# led_module.net
KiCad netlist of a schematic drawn in EAGLE
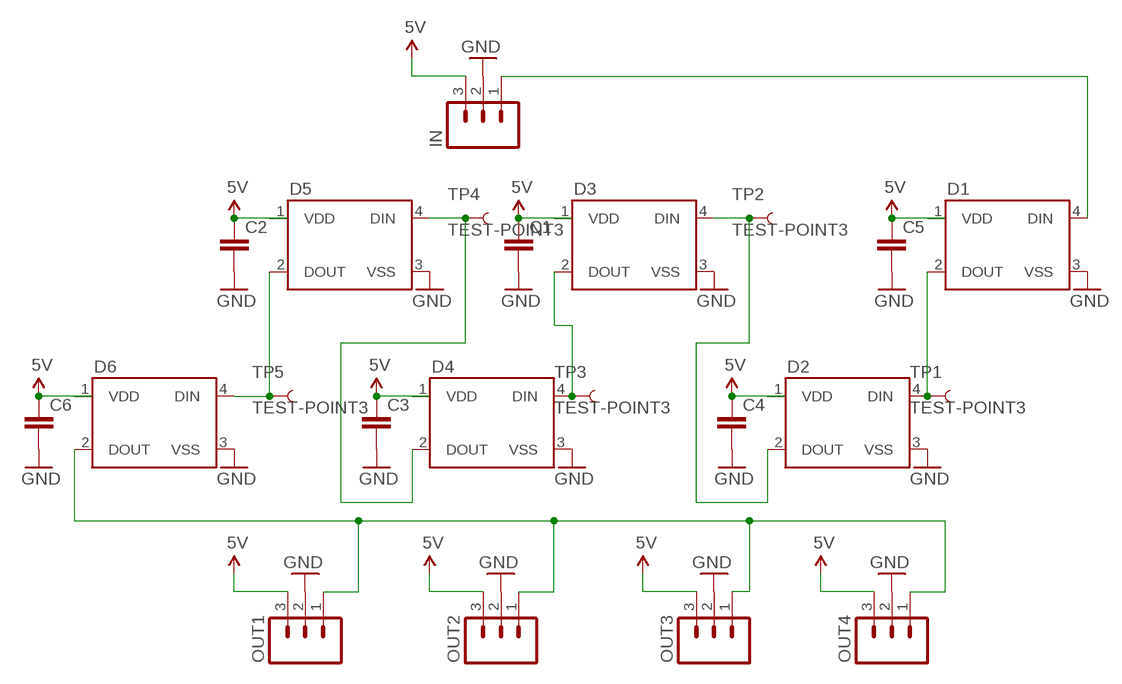
[diagram p0: schematic, sheet 1]

(export (version "E")
  (design (tool "Eeschema 10.0.6"))
  (components
    (comp (ref "C1")
      (value "CAP0805")
      (footprint "eagle-import:0805")
      (libsource (lib "eagle-import") (part "CAP0805"))
    )
    (comp (ref "C2")
      (value "CAP0805")
      (footprint "eagle-import:0805")
      (libsource (lib "eagle-import") (part "CAP0805"))
    )
    (comp (ref "C3")
      (value "CAP0805")
      (footprint "eagle-import:0805")
      (libsource (lib "eagle-import") (part "CAP0805"))
    )
    (comp (ref "C4")
      (value "CAP0805")
      (footprint "eagle-import:0805")
      (libsource (lib "eagle-import") (part "CAP0805"))
    )
    (comp (ref "C5")
      (value "CAP0805")
      (footprint "eagle-import:0805")
      (libsource (lib "eagle-import") (part "CAP0805"))
    )
    (comp (ref "C6")
      (value "CAP0805")
      (footprint "eagle-import:0805")
      (libsource (lib "eagle-import") (part "CAP0805"))
    )
    (comp (ref "D1")
      (value "WS2812B")
      (footprint "eagle-import:WS2812B")
      (libsource (lib "eagle-import") (part "WS2812B"))
    )
    (comp (ref "D2")
      (value "WS2812B")
      (footprint "eagle-import:WS2812B")
      (libsource (lib "eagle-import") (part "WS2812B"))
    )
    (comp (ref "D3")
      (value "WS2812B")
      (footprint "eagle-import:WS2812B")
      (libsource (lib "eagle-import") (part "WS2812B"))
    )
    (comp (ref "D4")
      (value "WS2812B")
      (footprint "eagle-import:WS2812B")
      (libsource (lib "eagle-import") (part "WS2812B"))
    )
    (comp (ref "D5")
      (value "WS2812B")
      (footprint "eagle-import:WS2812B")
      (libsource (lib "eagle-import") (part "WS2812B"))
    )
    (comp (ref "D6")
      (value "WS2812B")
      (footprint "eagle-import:WS2812B")
      (libsource (lib "eagle-import") (part "WS2812B"))
    )
    (comp (ref "IN")
      (value "M03LONGPADS")
      (footprint "eagle-import:1X03_LONGPADS")
      (libsource (lib "eagle-import") (part "M03LONGPADS"))
    )
    (comp (ref "OUT1")
      (value "M03LONGPADS")
      (footprint "eagle-import:1X03_LONGPADS")
      (libsource (lib "eagle-import") (part "M03LONGPADS"))
    )
    (comp (ref "OUT2")
      (value "M03LONGPADS")
      (footprint "eagle-import:1X03_LONGPADS")
      (libsource (lib "eagle-import") (part "M03LONGPADS"))
    )
    (comp (ref "OUT3")
      (value "M03LONGPADS")
      (footprint "eagle-import:1X03_LONGPADS")
      (libsource (lib "eagle-import") (part "M03LONGPADS"))
    )
    (comp (ref "OUT4")
      (value "M03LONGPADS")
      (footprint "eagle-import:1X03_LONGPADS")
      (libsource (lib "eagle-import") (part "M03LONGPADS"))
    )
    (comp (ref "TP1")
      (value "TEST-POINT3")
      (footprint "eagle-import:PAD.03X.03")
      (libsource (lib "eagle-import") (part "TEST-POINT3"))
    )
    (comp (ref "TP2")
      (value "TEST-POINT3")
      (footprint "eagle-import:PAD.03X.03")
      (libsource (lib "eagle-import") (part "TEST-POINT3"))
    )
    (comp (ref "TP3")
      (value "TEST-POINT3")
      (footprint "eagle-import:PAD.03X.03")
      (libsource (lib "eagle-import") (part "TEST-POINT3"))
    )
    (comp (ref "TP4")
      (value "TEST-POINT3")
      (footprint "eagle-import:PAD.03X.03")
      (libsource (lib "eagle-import") (part "TEST-POINT3"))
    )
    (comp (ref "TP5")
      (value "TEST-POINT3")
      (footprint "eagle-import:PAD.03X.03")
      (libsource (lib "eagle-import") (part "TEST-POINT3"))
    )
  )
  (nets
    (net (code "1") (name "5V") (class "Default")
      (node (ref "C1") (pin "1") (pinfunction "1_1") (pintype "passive"))
      (node (ref "C2") (pin "1") (pinfunction "1_1") (pintype "passive"))
      (node (ref "C3") (pin "1") (pinfunction "1_1") (pintype "passive"))
      (node (ref "C4") (pin "1") (pinfunction "1_1") (pintype "passive"))
      (node (ref "C5") (pin "1") (pinfunction "1_1") (pintype "passive"))
      (node (ref "C6") (pin "1") (pinfunction "1_1") (pintype "passive"))
      (node (ref "D1") (pin "1") (pinfunction "VDD_1") (pintype "power_in"))
      (node (ref "D2") (pin "1") (pinfunction "VDD_1") (pintype "power_in"))
      (node (ref "D3") (pin "1") (pinfunction "VDD_1") (pintype "power_in"))
      (node (ref "D4") (pin "1") (pinfunction "VDD_1") (pintype "power_in"))
      (node (ref "D5") (pin "1") (pinfunction "VDD_1") (pintype "power_in"))
      (node (ref "D6") (pin "1") (pinfunction "VDD_1") (pintype "power_in"))
      (node (ref "IN") (pin "3") (pinfunction "3_3") (pintype "passive"))
      (node (ref "OUT1") (pin "3") (pinfunction "3_3") (pintype "passive"))
      (node (ref "OUT2") (pin "3") (pinfunction "3_3") (pintype "passive"))
      (node (ref "OUT3") (pin "3") (pinfunction "3_3") (pintype "passive"))
      (node (ref "OUT4") (pin "3") (pinfunction "3_3") (pintype "passive"))
    )
    (net (code "2") (name "GND") (class "Default")
      (node (ref "C1") (pin "2") (pinfunction "2_2") (pintype "passive"))
      (node (ref "C2") (pin "2") (pinfunction "2_2") (pintype "passive"))
      (node (ref "C3") (pin "2") (pinfunction "2_2") (pintype "passive"))
      (node (ref "C4") (pin "2") (pinfunction "2_2") (pintype "passive"))
      (node (ref "C5") (pin "2") (pinfunction "2_2") (pintype "passive"))
      (node (ref "C6") (pin "2") (pinfunction "2_2") (pintype "passive"))
      (node (ref "D1") (pin "3") (pinfunction "VSS_3") (pintype "power_in"))
      (node (ref "D2") (pin "3") (pinfunction "VSS_3") (pintype "power_in"))
      (node (ref "D3") (pin "3") (pinfunction "VSS_3") (pintype "power_in"))
      (node (ref "D4") (pin "3") (pinfunction "VSS_3") (pintype "power_in"))
      (node (ref "D5") (pin "3") (pinfunction "VSS_3") (pintype "power_in"))
      (node (ref "D6") (pin "3") (pinfunction "VSS_3") (pintype "power_in"))
      (node (ref "IN") (pin "2") (pinfunction "2_2") (pintype "passive"))
      (node (ref "OUT1") (pin "2") (pinfunction "2_2") (pintype "passive"))
      (node (ref "OUT2") (pin "2") (pinfunction "2_2") (pintype "passive"))
      (node (ref "OUT3") (pin "2") (pinfunction "2_2") (pintype "passive"))
      (node (ref "OUT4") (pin "2") (pinfunction "2_2") (pintype "passive"))
    )
    (net (code "3") (name "Net-(D1-DIN)") (class "Default")
      (node (ref "D1") (pin "4") (pinfunction "DIN_4") (pintype "input"))
      (node (ref "IN") (pin "1") (pinfunction "1_1") (pintype "passive"))
    )
    (net (code "4") (name "Net-(D1-DOUT)") (class "Default")
      (node (ref "D1") (pin "2") (pinfunction "DOUT_2") (pintype "output"))
      (node (ref "D2") (pin "4") (pinfunction "DIN_4") (pintype "input"))
      (node (ref "TP1") (pin "P$1") (pinfunction "1_P$1") (pintype "bidirectional"))
    )
    (net (code "5") (name "Net-(D2-DOUT)") (class "Default")
      (node (ref "D2") (pin "2") (pinfunction "DOUT_2") (pintype "output"))
      (node (ref "D3") (pin "4") (pinfunction "DIN_4") (pintype "input"))
      (node (ref "TP2") (pin "P$1") (pinfunction "1_P$1") (pintype "bidirectional"))
    )
    (net (code "6") (name "Net-(D3-DOUT)") (class "Default")
      (node (ref "D3") (pin "2") (pinfunction "DOUT_2") (pintype "output"))
      (node (ref "D4") (pin "4") (pinfunction "DIN_4") (pintype "input"))
      (node (ref "TP3") (pin "P$1") (pinfunction "1_P$1") (pintype "bidirectional"))
    )
    (net (code "7") (name "Net-(D4-DOUT)") (class "Default")
      (node (ref "D4") (pin "2") (pinfunction "DOUT_2") (pintype "output"))
      (node (ref "D5") (pin "4") (pinfunction "DIN_4") (pintype "input"))
      (node (ref "TP4") (pin "P$1") (pinfunction "1_P$1") (pintype "bidirectional"))
    )
    (net (code "8") (name "Net-(D5-DOUT)") (class "Default")
      (node (ref "D5") (pin "2") (pinfunction "DOUT_2") (pintype "output"))
      (node (ref "D6") (pin "4") (pinfunction "DIN_4") (pintype "input"))
      (node (ref "TP5") (pin "P$1") (pinfunction "1_P$1") (pintype "bidirectional"))
    )
    (net (code "9") (name "Net-(D6-DOUT)") (class "Default")
      (node (ref "D6") (pin "2") (pinfunction "DOUT_2") (pintype "output"))
      (node (ref "OUT1") (pin "1") (pinfunction "1_1") (pintype "passive"))
      (node (ref "OUT2") (pin "1") (pinfunction "1_1") (pintype "passive"))
      (node (ref "OUT3") (pin "1") (pinfunction "1_1") (pintype "passive"))
      (node (ref "OUT4") (pin "1") (pinfunction "1_1") (pintype "passive"))
    )
  )
)
